# EasyPi_20210521.net
KiCad netlist of a schematic drawn in Altium Designer
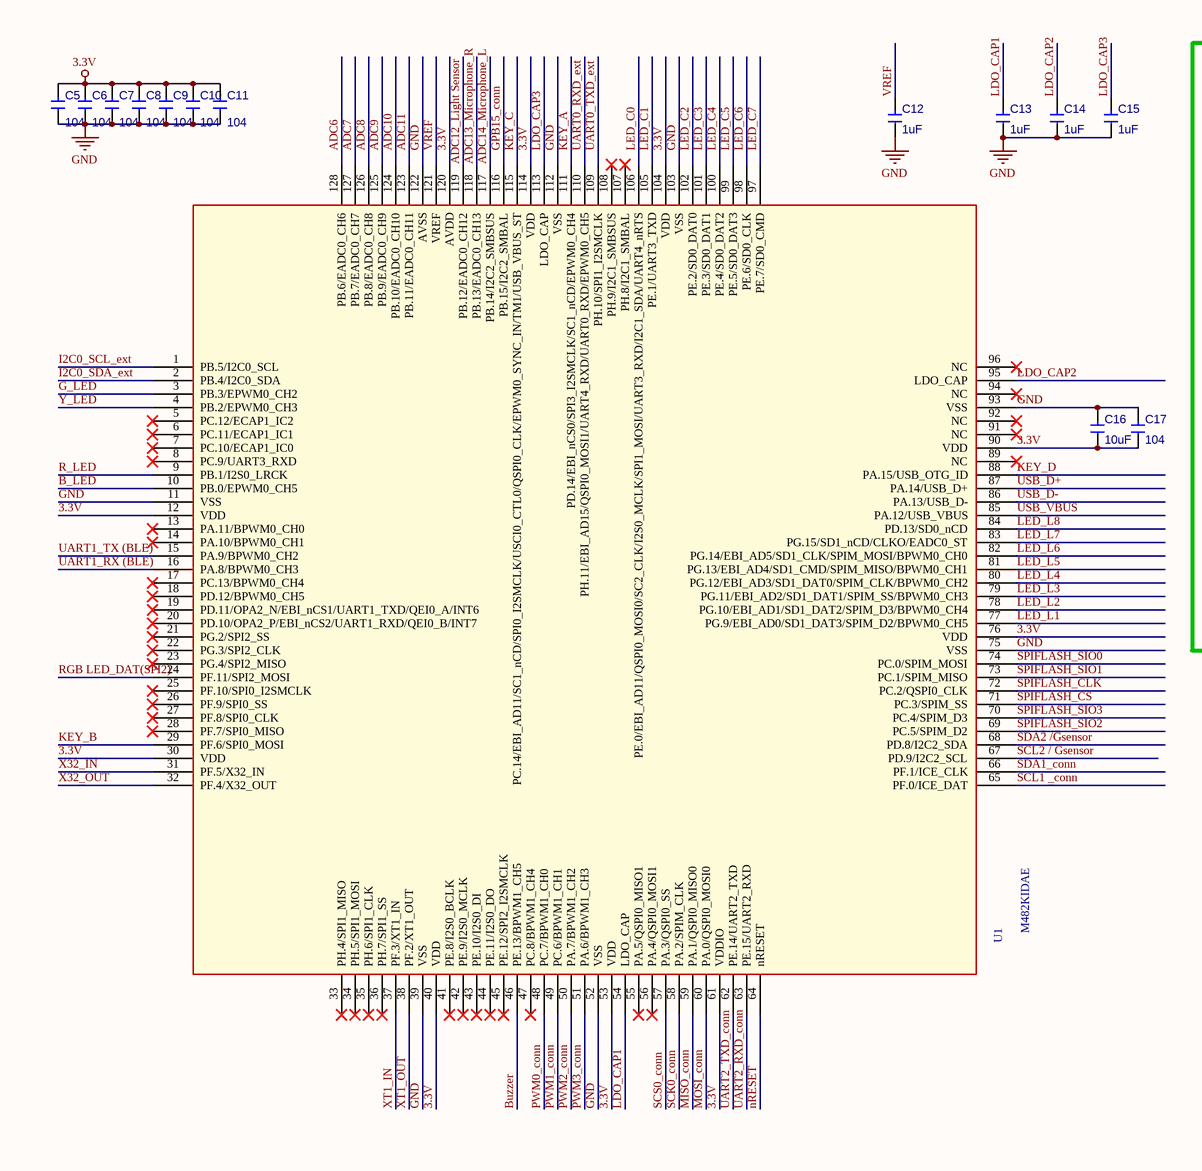
[diagram p0: EasyPi+ 20210521.SchDoc, top left]
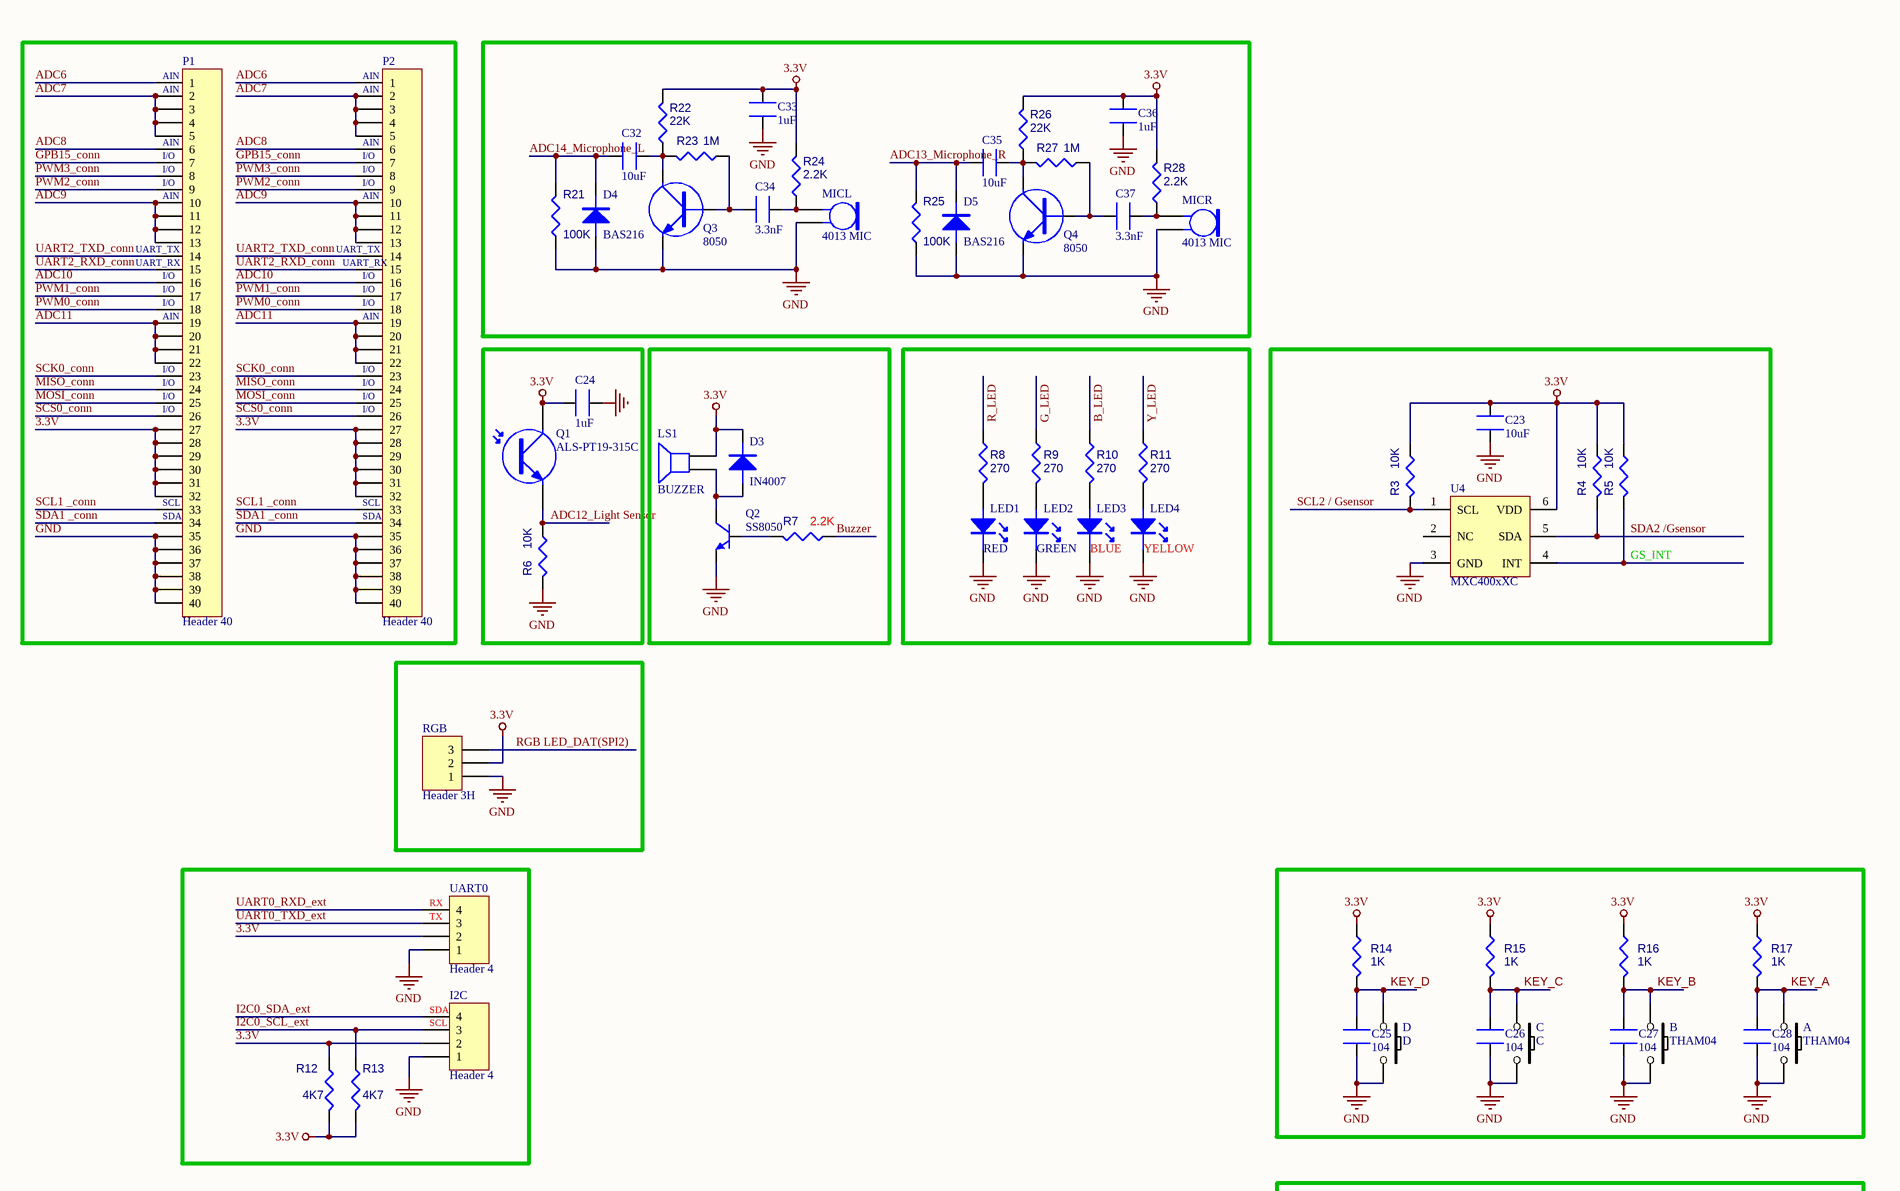
[diagram p1: EasyPi+ 20210521.SchDoc, top right]
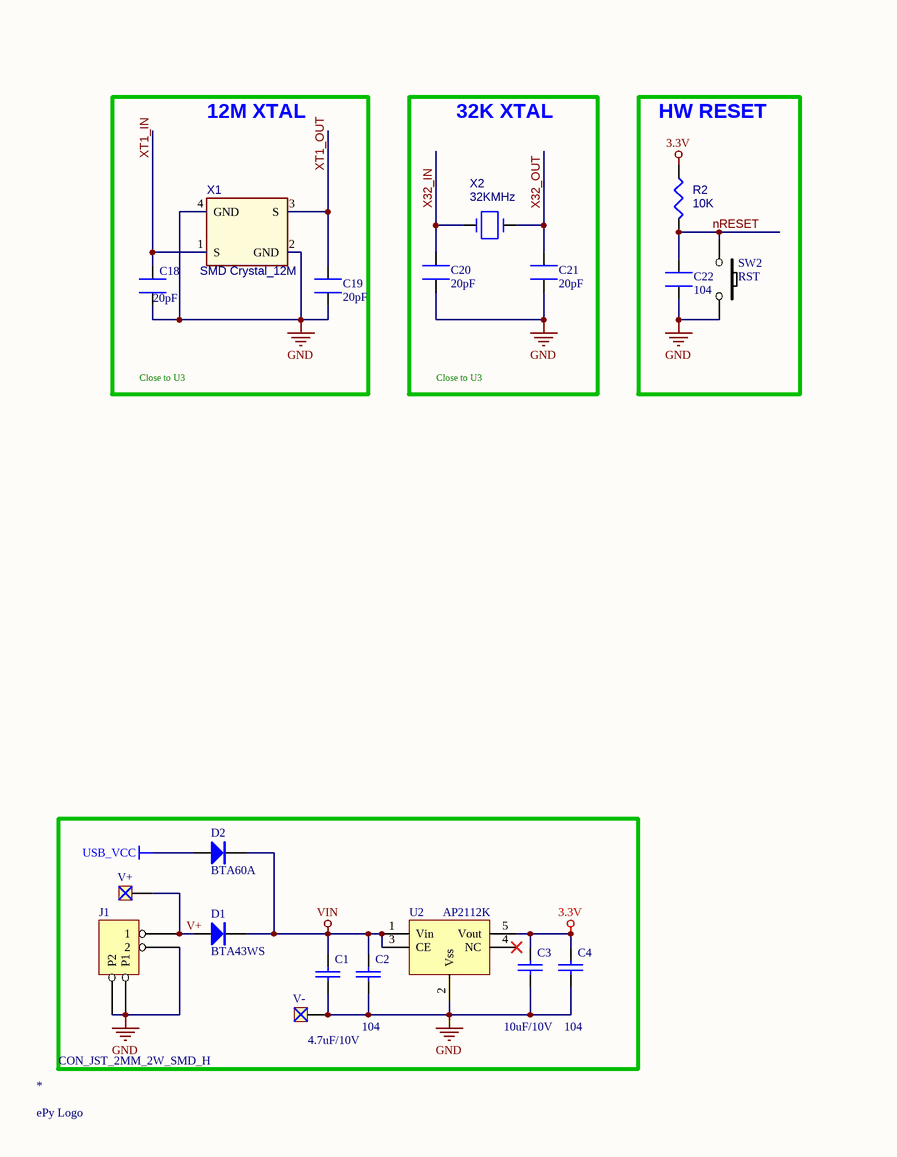
[diagram p2: EasyPi+ 20210521.SchDoc, bottom left]
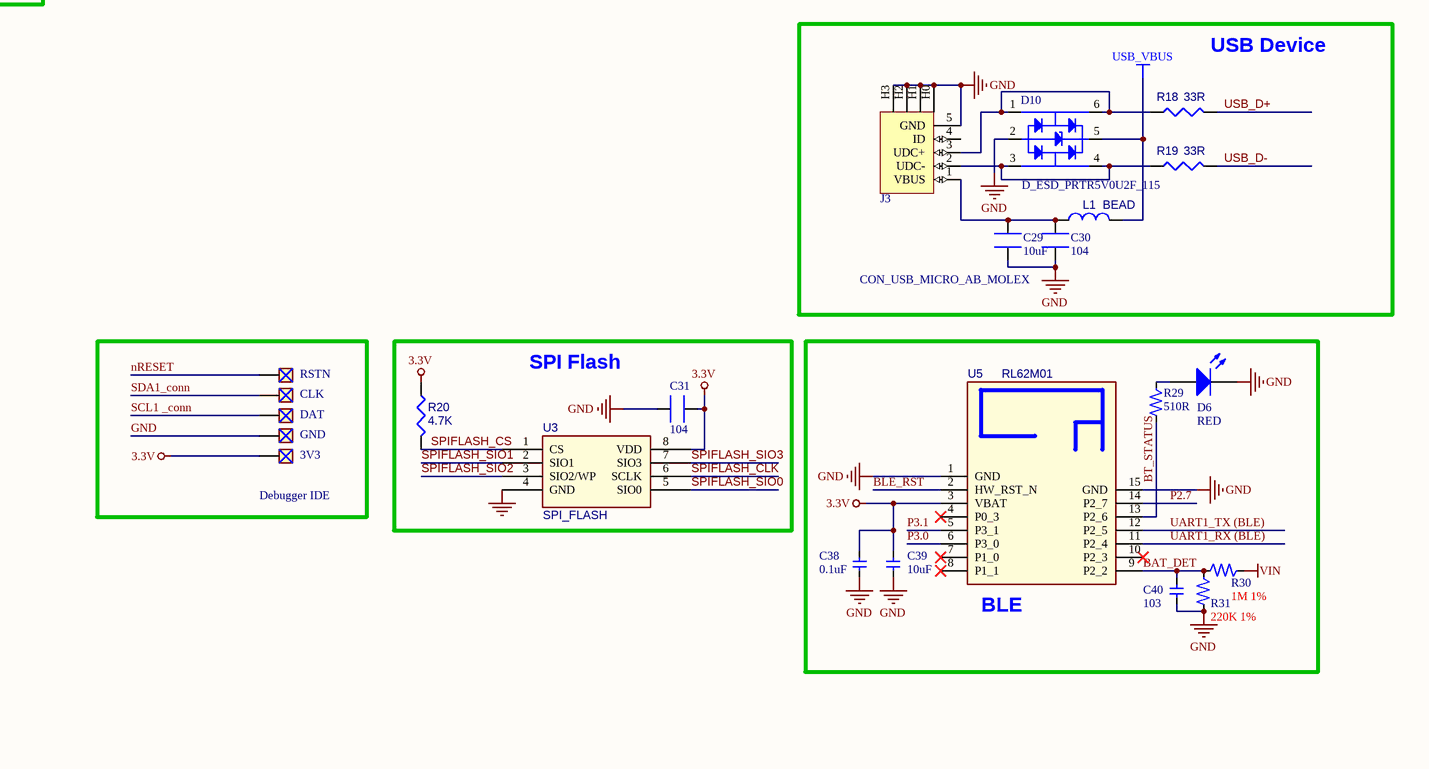
[diagram p3: EasyPi+ 20210521.SchDoc, bottom right]

(export (version "E")
  (design (tool "Eeschema 10.0.6"))
  (components
    (comp (ref "*") (value "ePy Logo") (footprint "ePi LOGO-M") (libsource (lib "Allen") (part "ePy Logo")))
    (comp (ref "3V3") (value "TERMINAL") (footprint "PAD-SMD") (libsource (lib "Allen") (part "TERMINAL")))
    (comp (ref "A") (value "THAM04") (footprint "TC-H-4415AA") (libsource (lib "Allen") (part "TC SWITCH")))
    (comp (ref "B") (value "THAM04") (footprint "TC-H-4415AA") (libsource (lib "Allen") (part "TC SWITCH")))
    (comp (ref "C") (value "C") (footprint "TC-H-4415AA") (libsource (lib "Allen") (part "TC SWITCH")))
    (comp (ref "C1")
      (value "4.7uF/10V")
      (footprint "C 0805")
      (description "CAP")
      (libsource (lib "") (part "CAP_1"))
    )
    (comp (ref "C2")
      (value "104")
      (footprint "C 0402")
      (description "CAP")
      (libsource (lib "") (part "CAP_1"))
    )
    (comp (ref "C3")
      (value "10uF/10V")
      (footprint "C 0402")
      (description "CAP")
      (libsource (lib "") (part "CAP_1"))
    )
    (comp (ref "C4")
      (value "104")
      (footprint "C 0402")
      (description "CAP")
      (libsource (lib "") (part "CAP_1"))
    )
    (comp (ref "C5")
      (value "104")
      (footprint "C 0402")
      (description "MC (R2HF) 1uF 10V 10%(K) X5R 0402 T=0.5mm CC0402KRX5R6BB105 YAGEO")
      (fields (field (name "PART_NUMBER") "150-226-0173R"))
      (libsource (lib "*") (part "CAP"))
    )
    (comp (ref "C6")
      (value "104")
      (footprint "C 0402")
      (description "MC (R2HF) 1uF 10V 10%(K) X5R 0402 T=0.5mm CC0402KRX5R6BB105 YAGEO")
      (fields (field (name "PART_NUMBER") "150-226-0173R"))
      (libsource (lib "*") (part "CAP"))
    )
    (comp (ref "C7")
      (value "104")
      (footprint "C 0402")
      (description "MC (R2HF) 1uF 10V 10%(K) X5R 0402 T=0.5mm CC0402KRX5R6BB105 YAGEO")
      (fields (field (name "PART_NUMBER") "150-226-0173R"))
      (libsource (lib "*") (part "CAP"))
    )
    (comp (ref "C8")
      (value "104")
      (footprint "C 0402")
      (description "MC (R2HF) 1uF 10V 10%(K) X5R 0402 T=0.5mm CC0402KRX5R6BB105 YAGEO")
      (fields (field (name "PART_NUMBER") "150-226-0173R"))
      (libsource (lib "*") (part "CAP"))
    )
    (comp (ref "C9")
      (value "104")
      (footprint "C 0402")
      (description "MC (R2HF) 1uF 10V 10%(K) X5R 0402 T=0.5mm CC0402KRX5R6BB105 YAGEO")
      (fields (field (name "PART_NUMBER") "150-226-0173R"))
      (libsource (lib "*") (part "CAP"))
    )
    (comp (ref "C10")
      (value "104")
      (footprint "C 0402")
      (description "MC (R2HF) 1uF 10V 10%(K) X5R 0402 T=0.5mm CC0402KRX5R6BB105 YAGEO")
      (fields (field (name "PART_NUMBER") "150-226-0173R"))
      (libsource (lib "*") (part "CAP"))
    )
    (comp (ref "C11")
      (value "104")
      (footprint "C 0402")
      (description "MC (R2HF) 1uF 10V 10%(K) X5R 0402 T=0.5mm CC0402KRX5R6BB105 YAGEO")
      (fields (field (name "PART_NUMBER") "150-226-0173R"))
      (libsource (lib "*") (part "CAP"))
    )
    (comp (ref "C12")
      (value "1uF")
      (footprint "C 0402")
      (description "MC (R2HF) 1uF 10V 10%(K) X5R 0402 T=0.5mm CC0402KRX5R6BB105 YAGEO")
      (fields (field (name "PART_NUMBER") "150-226-0173R"))
      (libsource (lib "*") (part "CAP"))
    )
    (comp (ref "C13")
      (value "1uF")
      (footprint "C 0402")
      (description "MC (R2HF) 1uF 10V 10%(K) X5R 0402 T=0.5mm CC0402KRX5R6BB105 YAGEO")
      (fields (field (name "PART_NUMBER") "150-226-0173R"))
      (libsource (lib "*") (part "CAP"))
    )
    (comp (ref "C14")
      (value "1uF")
      (footprint "C 0402")
      (description "MC (R2HF) 1uF 10V 10%(K) X5R 0402 T=0.5mm CC0402KRX5R6BB105 YAGEO")
      (fields (field (name "PART_NUMBER") "150-226-0173R"))
      (libsource (lib "*") (part "CAP"))
    )
    (comp (ref "C15")
      (value "1uF")
      (footprint "C 0402")
      (description "MC (R2HF) 1uF 10V 10%(K) X5R 0402 T=0.5mm CC0402KRX5R6BB105 YAGEO")
      (fields (field (name "PART_NUMBER") "150-226-0173R"))
      (libsource (lib "*") (part "CAP"))
    )
    (comp (ref "C16")
      (value "10uF")
      (footprint "C 0402")
      (description "MC (R2HF) 1uF 10V 10%(K) X5R 0402 T=0.5mm CC0402KRX5R6BB105 YAGEO")
      (fields (field (name "PART_NUMBER") "150-226-0173R"))
      (libsource (lib "*") (part "CAP"))
    )
    (comp (ref "C17")
      (value "104")
      (footprint "C 0402")
      (description "MC (R2HF) 1uF 10V 10%(K) X5R 0402 T=0.5mm CC0402KRX5R6BB105 YAGEO")
      (fields (field (name "PART_NUMBER") "150-226-0173R"))
      (libsource (lib "*") (part "CAP"))
    )
    (comp (ref "C18") (value "20pF") (footprint "C 0402") (libsource (lib "Allen") (part "CAP")))
    (comp (ref "C19") (value "20pF") (footprint "C 0402") (libsource (lib "Allen") (part "CAP")))
    (comp (ref "C20") (value "20pF") (footprint "C 0402") (libsource (lib "Allen") (part "CAP")))
    (comp (ref "C21") (value "20pF") (footprint "C 0402") (libsource (lib "Allen") (part "CAP")))
    (comp (ref "C22") (value "104") (footprint "C 0402") (libsource (lib "Allen") (part "CAP")))
    (comp (ref "C23") (value "10uF") (footprint "C 0402") (libsource (lib "Allen") (part "CAP")))
    (comp (ref "C24") (value "1uF") (footprint "C 0402") (libsource (lib "Allen") (part "CAP")))
    (comp (ref "C25") (value "104") (footprint "C 0402") (libsource (lib "Allen") (part "CAP")))
    (comp (ref "C26") (value "104") (footprint "C 0402") (libsource (lib "Allen") (part "CAP")))
    (comp (ref "C27") (value "104") (footprint "C 0402") (libsource (lib "Allen") (part "CAP")))
    (comp (ref "C28") (value "104") (footprint "C 0402") (libsource (lib "Allen") (part "CAP")))
    (comp (ref "C29") (value "10uF") (footprint "C 0402") (libsource (lib "Allen") (part "CAP")))
    (comp (ref "C30") (value "104") (footprint "C 0402") (libsource (lib "Allen") (part "CAP")))
    (comp (ref "C31") (value "104") (footprint "C 0603") (libsource (lib "Allen") (part "CAP")))
    (comp (ref "C32") (value "10uF") (footprint "C 0402") (libsource (lib "Allen") (part "CAP")))
    (comp (ref "C33") (value "1uF") (footprint "C 0402") (libsource (lib "Allen") (part "CAP")))
    (comp (ref "C34") (value "3.3nF") (footprint "C 0402") (libsource (lib "Allen") (part "CAP")))
    (comp (ref "C35") (value "10uF") (footprint "C 0402") (libsource (lib "Allen") (part "CAP")))
    (comp (ref "C36") (value "1uF") (footprint "C 0402") (libsource (lib "Allen") (part "CAP")))
    (comp (ref "C37") (value "3.3nF") (footprint "C 0402") (libsource (lib "Allen") (part "CAP")))
    (comp (ref "C38") (value "0.1uF") (footprint "C 0402") (libsource (lib "Allen") (part "CAP/S")))
    (comp (ref "C39") (value "10uF") (footprint "C 0402") (libsource (lib "Allen") (part "CAP/S")))
    (comp (ref "C40") (value "103") (footprint "C 0402") (libsource (lib "Allen") (part "CAP/S")))
    (comp (ref "CLK") (value "TERMINAL") (footprint "PAD-SMD") (libsource (lib "Allen") (part "TERMINAL")))
    (comp (ref "D") (value "D") (footprint "TC-H-4415AA") (libsource (lib "Allen") (part "TC SWITCH")))
    (comp (ref "D1")
      (value "BTA43WS")
      (footprint "SOD-323")
      (description "快恢复整流二极管")
      (fields (field (name "版权归属") "黎明电子style"))
      (libsource (lib "二极管-整流桥") (part "FFM107"))
    )
    (comp (ref "D2")
      (value "BTA60A")
      (footprint "SOD-323")
      (description "快恢复整流二极管")
      (fields (field (name "版权归属") "黎明电子style"))
      (libsource (lib "二极管-整流桥") (part "FFM107"))
    )
    (comp (ref "D3") (value "IN4007") (footprint "SOD-123F") (libsource (lib "Allen") (part "DIODE")))
    (comp (ref "D4") (value "BAS216") (footprint "SOD123") (libsource (lib "Allen") (part "DIODE")))
    (comp (ref "D5") (value "BAS216") (footprint "SOD123") (libsource (lib "Allen") (part "DIODE")))
    (comp (ref "D6")
      (value "RED")
      (footprint "LED 0603R")
      (description "Typical RED, GREEN, YELLOW, AMBER GaAs LED")
      (fields (field (name "PUBLISHER") "Altium Limited"))
      (libsource (lib "Miscellaneous Devices") (part "LED2"))
    )
    (comp (ref "D10")
      (value "D_ESD_PRTR5V0U2F_115")
      (footprint "SOT886")
      (description "Ultra low capacitance double rail-to-rail ESD protection")
      (fields (field (name "MANUFACTURER") "NXP") (field (name "PART") "PRTR5V0U2F_115"))
      (libsource (lib "Allen") (part "D_ESD_PRTR5V0U2F_115"))
    )
    (comp (ref "DAT") (value "TERMINAL") (footprint "PAD-SMD") (libsource (lib "Allen") (part "TERMINAL")))
    (comp (ref "GND") (value "TERMINAL") (footprint "PAD-SMD") (libsource (lib "Allen") (part "TERMINAL")))
    (comp (ref "I2C")
      (value "Header 4")
      (footprint "XH2.54-4P")
      (description "Header, 4-Pin")
      (fields (field (name "PUBLISHER") "Altium Limited"))
      (libsource (lib "Miscellaneous Connectors") (part "Header 4"))
    )
    (comp (ref "J1")
      (value "CON_JST_2MM_2W_SMD_H")
      (footprint "CON_JST_S2B-PH-SM4-TB")
      (description "2 PIN 2MM SMT JST  CONNECTOR")
      (fields (field (name "PART") "S2B-PH-SM4-TB(LF)(SN)") (field (name "MANUFACTURER") "JST"))
      (libsource (lib "Arbury_CON") (part "CON_JST_2MM_2W_SMD_H"))
    )
    (comp (ref "J3")
      (value "CON_USB_MICRO_AB_MOLEX")
      (footprint "CON_USB_MICRO_AB_MOLEX")
      (description "USB Micro-AB socket Molex 47589-0001")
      (fields (field (name "PART") "47589-0001") (field (name "MANUFACTURER") "Molex"))
      (libsource (lib "Allen") (part "CON_USB_MICRO_AB_MOLEX"))
    )
    (comp (ref "L1") (value "BEAD") (footprint "L 0603") (libsource (lib "*") (part "FB_0603")))
    (comp (ref "LED1") (value "RED") (footprint "LED-0603") (libsource (lib "Allen") (part "LED")))
    (comp (ref "LED2") (value "GREEN") (footprint "LED-0603") (libsource (lib "Allen") (part "LED")))
    (comp (ref "LED3") (value "BLUE") (footprint "LED-0603") (libsource (lib "Allen") (part "LED")))
    (comp (ref "LED4") (value "YELLOW") (footprint "LED-0603") (libsource (lib "Allen") (part "LED")))
    (comp (ref "LS1")
      (value "BUZZER")
      (footprint "BUZER 8530")
      (description "Loudspeaker")
      (fields (field (name "PUBLISHER") "Altium Limited"))
      (libsource (lib "Miscellaneous Devices") (part "Speaker"))
    )
    (comp (ref "MICL")
      (value "4013 MIC")
      (footprint "4013 MIC")
      (description "Microphone")
      (fields (field (name "PUBLISHER") "Altium Limited"))
      (libsource (lib "Miscellaneous Devices") (part "Mic2"))
    )
    (comp (ref "MICR")
      (value "4013 MIC")
      (footprint "4013 MIC")
      (description "Microphone")
      (fields (field (name "PUBLISHER") "Altium Limited"))
      (libsource (lib "Miscellaneous Devices") (part "Mic2"))
    )
    (comp (ref "P1")
      (value "Header 40")
      (footprint "HEADER40")
      (description "Header, 40-Pin")
      (fields (field (name "PUBLISHER") "Altium Limited"))
      (libsource (lib "Allen") (part "Header 40"))
    )
    (comp (ref "P2")
      (value "Header 40")
      (footprint "HEADER40")
      (description "Header, 40-Pin")
      (fields (field (name "PUBLISHER") "Altium Limited"))
      (libsource (lib "Allen") (part "Header 40"))
    )
    (comp (ref "Q1")
      (value "ALS-PT19-315C")
      (footprint "ALS-PT19-315C")
      (description "NPN Phototransistor")
      (fields (field (name "PUBLISHER") "Altium Limited"))
      (libsource (lib "Allen") (part "Photo NPN"))
    )
    (comp (ref "Q2")
      (value "SS8050")
      (footprint "SOT23-3N")
      (description "高频放大-NPN型")
      (fields (field (name "版权归属") "黎明电子style"))
      (libsource (lib "三极管") (part "8050-SMD"))
    )
    (comp (ref "Q3")
      (value "8050")
      (footprint "SOT23-3")
      (description "NPN")
      (libsource (lib "Allen") (part "NPN"))
    )
    (comp (ref "Q4")
      (value "8050")
      (footprint "SOT23-3")
      (description "NPN")
      (libsource (lib "Allen") (part "NPN"))
    )
    (comp (ref "R2") (value "10K") (footprint "R 0402") (libsource (lib "*") (part "R")))
    (comp (ref "R3") (value "10K") (footprint "R 0402") (libsource (lib "*") (part "R")))
    (comp (ref "R4") (value "10K") (footprint "R 0402") (libsource (lib "*") (part "R")))
    (comp (ref "R5") (value "10K") (footprint "R 0402") (libsource (lib "*") (part "R")))
    (comp (ref "R6") (value "10K") (footprint "R 0402") (libsource (lib "*") (part "R")))
    (comp (ref "R7") (value "2.2K") (footprint "R 0402") (libsource (lib "*") (part "R")))
    (comp (ref "R8") (value "270") (footprint "R 0402") (libsource (lib "*") (part "R")))
    (comp (ref "R9") (value "270") (footprint "R 0402") (libsource (lib "*") (part "R")))
    (comp (ref "R10") (value "270") (footprint "R 0402") (libsource (lib "*") (part "R")))
    (comp (ref "R11") (value "270") (footprint "R 0402") (libsource (lib "*") (part "R")))
    (comp (ref "R12") (value "4K7") (footprint "R 0402") (libsource (lib "*") (part "R")))
    (comp (ref "R13") (value "4K7") (footprint "R 0402") (libsource (lib "*") (part "R")))
    (comp (ref "R14") (value "1K") (footprint "R 0402") (libsource (lib "*") (part "R")))
    (comp (ref "R15") (value "1K") (footprint "R 0402") (libsource (lib "*") (part "R")))
    (comp (ref "R16") (value "1K") (footprint "R 0402") (libsource (lib "*") (part "R")))
    (comp (ref "R17") (value "1K") (footprint "R 0402") (libsource (lib "*") (part "R")))
    (comp (ref "R18") (value "33R") (footprint "R 0402") (libsource (lib "*") (part "R")))
    (comp (ref "R19") (value "33R") (footprint "R 0402") (libsource (lib "*") (part "R")))
    (comp (ref "R20") (value "4.7K") (footprint "R 0603") (libsource (lib "*") (part "R")))
    (comp (ref "R21") (value "100K") (footprint "R 0402") (libsource (lib "*") (part "R")))
    (comp (ref "R22") (value "22K") (footprint "R 0402") (libsource (lib "*") (part "R")))
    (comp (ref "R23") (value "1M") (footprint "R 0402") (libsource (lib "*") (part "R")))
    (comp (ref "R24") (value "2.2K") (footprint "R 0402") (libsource (lib "*") (part "R")))
    (comp (ref "R25") (value "100K") (footprint "R 0402") (libsource (lib "*") (part "R")))
    (comp (ref "R26") (value "22K") (footprint "R 0402") (libsource (lib "*") (part "R")))
    (comp (ref "R27") (value "1M") (footprint "R 0402") (libsource (lib "*") (part "R")))
    (comp (ref "R28") (value "2.2K") (footprint "R 0402") (libsource (lib "*") (part "R")))
    (comp (ref "R29") (value "510R") (footprint "R 0402") (libsource (lib "Allen") (part "RES1_30")))
    (comp (ref "R30") (value "1M 1%") (footprint "R 0603") (libsource (lib "Allen") (part "RES1_30")))
    (comp (ref "R31") (value "220K 1%") (footprint "R 0603") (libsource (lib "Allen") (part "RES1_30")))
    (comp (ref "RGB")
      (value "Header 3H")
      (footprint "A1254WR-S-03P")
      (description "Header, 3-Pin, Right Angle")
      (fields (field (name "PUBLISHER") "Altium Limited"))
      (libsource (lib "Miscellaneous Connectors") (part "Header 3H"))
    )
    (comp (ref "RSTN") (value "TERMINAL") (footprint "PAD-SMD") (libsource (lib "Allen") (part "TERMINAL")))
    (comp (ref "SW2")
      (value "RST")
      (footprint "T.SW/SMD/3x4 - NP")
      (libsource (lib "Allen") (part "TC SWITCH"))
    )
    (comp (ref "U1")
      (value "M482KIDAE")
      (footprint "LQFP128 14x14_N")
      (libsource (lib "M482KIDAE") (part "M482KIDAE"))
    )
    (comp (ref "U2") (value "AP2112K") (footprint "SOT23-5L") (libsource (lib "Allen") (part "XC6204")))
    (comp (ref "U3")
      (value "SPI_FLASH")
      (footprint "VSOP8 - 208mil")
      (description "IC FLASH (R) GD25Q128CSIG SOP-8 128MX1/64MX2/32MX4 2.7~3.6V SPI INDUSTRIAL GIGADEVICE")
      (libsource (lib "*") (part "FLASH-Serial 8pin-91_0"))
    )
    (comp (ref "U4") (value "MXC400xXC") (footprint "MXC400xXC") (libsource (lib "Allen") (part "MXC400xXC")))
    (comp (ref "U5") (value "RL62M01") (footprint "RL62M01A") (libsource (lib "Allen") (part "RL62M01")))
    (comp (ref "UART0")
      (value "Header 4")
      (footprint "XH2.54-4P")
      (description "Header, 4-Pin")
      (fields (field (name "PUBLISHER") "Altium Limited"))
      (libsource (lib "Miscellaneous Connectors") (part "Header 4"))
    )
    (comp (ref "V+") (value "PIN") (footprint "PAD-SMD") (libsource (lib "Allen") (part "PIN")))
    (comp (ref "V-") (value "PIN1") (footprint "PAD-SMD") (libsource (lib "Allen") (part "PIN")))
    (comp (ref "X1")
      (value "SMD Crystal_12M")
      (footprint "XTAL-3225")
      (libsource (lib "*") (part "XTAL_SMD"))
    )
    (comp (ref "X2") (value "32KMHz") (footprint "XTAL-3215") (libsource (lib "*") (part "CRYSTAL/SM")))
  )
  (nets
    (net (code "1") (name "/ADC6") (class "Default")
      (node (ref "P1") (pin "1") (pinfunction "1_1") (pintype "passive"))
      (node (ref "P2") (pin "1") (pinfunction "1_1") (pintype "passive"))
      (node (ref "U1") (pin "128") (pinfunction "PB.6/EADC0_CH6_128") (pintype "passive"))
    )
    (net (code "2") (name "/ADC7") (class "Default")
      (node (ref "P1") (pin "2") (pinfunction "2_2") (pintype "passive"))
      (node (ref "P1") (pin "3") (pinfunction "3_3") (pintype "passive"))
      (node (ref "P1") (pin "4") (pinfunction "4_4") (pintype "passive"))
      (node (ref "P1") (pin "5") (pinfunction "5_5") (pintype "passive"))
      (node (ref "P2") (pin "2") (pinfunction "2_2") (pintype "passive"))
      (node (ref "P2") (pin "3") (pinfunction "3_3") (pintype "passive"))
      (node (ref "P2") (pin "4") (pinfunction "4_4") (pintype "passive"))
      (node (ref "P2") (pin "5") (pinfunction "5_5") (pintype "passive"))
      (node (ref "U1") (pin "127") (pinfunction "PB.7/EADC0_CH7_127") (pintype "passive"))
    )
    (net (code "3") (name "/ADC8") (class "Default")
      (node (ref "P1") (pin "6") (pinfunction "6_6") (pintype "passive"))
      (node (ref "P2") (pin "6") (pinfunction "6_6") (pintype "passive"))
      (node (ref "U1") (pin "126") (pinfunction "PB.8/EADC0_CH8_126") (pintype "passive"))
    )
    (net (code "4") (name "/ADC9") (class "Default")
      (node (ref "P1") (pin "10") (pinfunction "10_10") (pintype "passive"))
      (node (ref "P1") (pin "11") (pinfunction "11_11") (pintype "passive"))
      (node (ref "P1") (pin "12") (pinfunction "12_12") (pintype "passive"))
      (node (ref "P1") (pin "13") (pinfunction "13_13") (pintype "passive"))
      (node (ref "P2") (pin "10") (pinfunction "10_10") (pintype "passive"))
      (node (ref "P2") (pin "11") (pinfunction "11_11") (pintype "passive"))
      (node (ref "P2") (pin "12") (pinfunction "12_12") (pintype "passive"))
      (node (ref "P2") (pin "13") (pinfunction "13_13") (pintype "passive"))
      (node (ref "U1") (pin "125") (pinfunction "PB.9/EADC0_CH9_125") (pintype "passive"))
    )
    (net (code "5") (name "/ADC10") (class "Default")
      (node (ref "P1") (pin "16") (pinfunction "16_16") (pintype "passive"))
      (node (ref "P2") (pin "16") (pinfunction "16_16") (pintype "passive"))
      (node (ref "U1") (pin "124") (pinfunction "PB.10/EADC0_CH10_124") (pintype "passive"))
    )
    (net (code "6") (name "/ADC11") (class "Default")
      (node (ref "P1") (pin "19") (pinfunction "19_19") (pintype "passive"))
      (node (ref "P1") (pin "20") (pinfunction "20_20") (pintype "passive"))
      (node (ref "P1") (pin "21") (pinfunction "21_21") (pintype "passive"))
      (node (ref "P1") (pin "22") (pinfunction "22_22") (pintype "passive"))
      (node (ref "P2") (pin "19") (pinfunction "19_19") (pintype "passive"))
      (node (ref "P2") (pin "20") (pinfunction "20_20") (pintype "passive"))
      (node (ref "P2") (pin "21") (pinfunction "21_21") (pintype "passive"))
      (node (ref "P2") (pin "22") (pinfunction "22_22") (pintype "passive"))
      (node (ref "U1") (pin "123") (pinfunction "PB.11/EADC0_CH11_123") (pintype "passive"))
    )
    (net (code "7") (name "/ADC12_Light Sensor") (class "Default")
      (node (ref "Q1") (pin "2") (pinfunction "2_2") (pintype "passive"))
      (node (ref "R6") (pin "1") (pinfunction "1_1") (pintype "passive"))
      (node (ref "U1") (pin "119") (pinfunction "PB.12/EADC0_CH12_119") (pintype "passive"))
    )
    (net (code "8") (name "/ADC13_Microphone_R") (class "Default")
      (node (ref "C35") (pin "1") (pinfunction "1_1") (pintype "passive"))
      (node (ref "D5") (pin "2") (pinfunction "K_2") (pintype "passive"))
      (node (ref "R25") (pin "2") (pinfunction "2_2") (pintype "passive"))
      (node (ref "U1") (pin "118") (pinfunction "PB.13/EADC0_CH13_118") (pintype "passive"))
    )
    (net (code "9") (name "/ADC14_Microphone_L") (class "Default")
      (node (ref "C32") (pin "1") (pinfunction "1_1") (pintype "passive"))
      (node (ref "D4") (pin "2") (pinfunction "K_2") (pintype "passive"))
      (node (ref "R21") (pin "2") (pinfunction "2_2") (pintype "passive"))
      (node (ref "U1") (pin "117") (pinfunction "PB.14/I2C2_SMBSUS_117") (pintype "passive"))
    )
    (net (code "10") (name "/BAT_DET") (class "Default")
      (node (ref "C40") (pin "1") (pinfunction "1_1") (pintype "passive"))
      (node (ref "R30") (pin "1") (pintype "passive"))
      (node (ref "R31") (pin "2") (pintype "passive"))
      (node (ref "U5") (pin "9") (pinfunction "P2_2_9") (pintype "passive"))
    )
    (net (code "11") (name "/BLE_RST") (class "Default")
      (node (ref "U5") (pin "2") (pinfunction "HW_RST_N_2") (pintype "passive"))
    )
    (net (code "12") (name "/BT_STATUS") (class "Default")
      (node (ref "R29") (pin "1") (pintype "passive"))
      (node (ref "U5") (pin "13") (pinfunction "P2_6_13") (pintype "passive"))
    )
    (net (code "13") (name "/B_LED") (class "Default")
      (node (ref "R10") (pin "1") (pinfunction "1_1") (pintype "passive"))
      (node (ref "U1") (pin "10") (pinfunction "PB.0/EPWM0_CH5_10") (pintype "passive"))
    )
    (net (code "14") (name "/Buzzer") (class "Default")
      (node (ref "R7") (pin "1") (pinfunction "1_1") (pintype "passive"))
      (node (ref "U1") (pin "46") (pinfunction "PE.13/BPWM1_CH5_46") (pintype "passive"))
    )
    (net (code "15") (name "/GPB15_conn") (class "Default")
      (node (ref "P1") (pin "7") (pinfunction "7_7") (pintype "passive"))
      (node (ref "P2") (pin "7") (pinfunction "7_7") (pintype "passive"))
      (node (ref "U1") (pin "116") (pinfunction "PB.15/I2C2_SMBAL_116") (pintype "passive"))
    )
    (net (code "16") (name "/GS_INT") (class "Default")
      (node (ref "R5") (pin "2") (pinfunction "2_2") (pintype "passive"))
      (node (ref "U4") (pin "4") (pinfunction "INT_4") (pintype "passive"))
    )
    (net (code "17") (name "/G_LED") (class "Default")
      (node (ref "R9") (pin "1") (pinfunction "1_1") (pintype "passive"))
      (node (ref "U1") (pin "3") (pinfunction "PB.3/EPWM0_CH2_3") (pintype "passive"))
    )
    (net (code "18") (name "/I2C0_SCL_ext") (class "Default")
      (node (ref "I2C") (pin "3") (pinfunction "3_3") (pintype "passive"))
      (node (ref "R13") (pin "1") (pinfunction "1_1") (pintype "passive"))
      (node (ref "U1") (pin "1") (pinfunction "PB.5/I2C0_SCL_1") (pintype "passive"))
    )
    (net (code "19") (name "/I2C0_SDA_ext") (class "Default")
      (node (ref "I2C") (pin "4") (pinfunction "4_4") (pintype "passive"))
      (node (ref "U1") (pin "2") (pinfunction "PB.4/I2C0_SDA_2") (pintype "passive"))
    )
    (net (code "20") (name "/KEY_A") (class "Default")
      (node (ref "A") (pin "1") (pinfunction "1_1") (pintype "passive"))
      (node (ref "C28") (pin "1") (pinfunction "1_1") (pintype "passive"))
      (node (ref "R17") (pin "2") (pinfunction "2_2") (pintype "passive"))
      (node (ref "U1") (pin "111") (pinfunction "PD.14/EBI_nCS0/SPI3_I2SMCLK/SC1_nCD/EPWM0_CH4_111") (pintype "passive"))
    )
    (net (code "21") (name "/KEY_B") (class "Default")
      (node (ref "B") (pin "1") (pinfunction "1_1") (pintype "passive"))
      (node (ref "C27") (pin "1") (pinfunction "1_1") (pintype "passive"))
      (node (ref "R16") (pin "2") (pinfunction "2_2") (pintype "passive"))
      (node (ref "U1") (pin "29") (pinfunction "PF.6/SPI0_MOSI_29") (pintype "passive"))
    )
    (net (code "22") (name "/KEY_C") (class "Default")
      (node (ref "C") (pin "1") (pinfunction "1_1") (pintype "passive"))
      (node (ref "C26") (pin "1") (pinfunction "1_1") (pintype "passive"))
      (node (ref "R15") (pin "2") (pinfunction "2_2") (pintype "passive"))
      (node (ref "U1") (pin "115") (pinfunction "PC.14/EBI_AD11/SC1_nCD/SPI0_I2SMCLK/USCI0_CTL0/QSPI0_CLK/EPWM0_SYNC_IN/TM1/USB_VBUS_ST_115") (pintype "passive"))
    )
    (net (code "23") (name "/KEY_D") (class "Default")
      (node (ref "C25") (pin "1") (pinfunction "1_1") (pintype "passive"))
      (node (ref "D") (pin "1") (pinfunction "1_1") (pintype "passive"))
      (node (ref "R14") (pin "2") (pinfunction "2_2") (pintype "passive"))
      (node (ref "U1") (pin "88") (pinfunction "PA.15/USB_OTG_ID_88") (pintype "passive"))
    )
    (net (code "24") (name "/LDO_CAP1") (class "Default")
      (node (ref "C13") (pin "2") (pinfunction "2_2") (pintype "passive"))
      (node (ref "U1") (pin "54") (pinfunction "LDO_CAP_54") (pintype "passive"))
    )
    (net (code "25") (name "/LDO_CAP2") (class "Default")
      (node (ref "C14") (pin "2") (pinfunction "2_2") (pintype "passive"))
      (node (ref "U1") (pin "95") (pinfunction "LDO_CAP_95") (pintype "passive"))
    )
    (net (code "26") (name "/LDO_CAP3") (class "Default")
      (node (ref "C15") (pin "2") (pinfunction "2_2") (pintype "passive"))
      (node (ref "U1") (pin "113") (pinfunction "LDO_CAP_113") (pintype "passive"))
    )
    (net (code "27") (name "/LED_C0") (class "Default")
      (node (ref "U1") (pin "106") (pinfunction "PE.0/EBI_AD11/QSPI0_MOSI0/SC2_CLK/I2S0_MCLK/SPI1_MOSI/UART3_RXD/I2C1_SDA/UART4_nRTS_106") (pintype "passive"))
    )
    (net (code "28") (name "/LED_C1") (class "Default")
      (node (ref "U1") (pin "105") (pinfunction "PE.1/UART3_TXD_105") (pintype "passive"))
    )
    (net (code "29") (name "/LED_C2") (class "Default")
      (node (ref "U1") (pin "102") (pinfunction "PE.2/SD0_DAT0_102") (pintype "passive"))
    )
    (net (code "30") (name "/LED_C3") (class "Default")
      (node (ref "U1") (pin "101") (pinfunction "PE.3/SD0_DAT1_101") (pintype "passive"))
    )
    (net (code "31") (name "/LED_C4") (class "Default")
      (node (ref "U1") (pin "100") (pinfunction "PE.4/SD0_DAT2_100") (pintype "passive"))
    )
    (net (code "32") (name "/LED_C5") (class "Default")
      (node (ref "U1") (pin "99") (pinfunction "PE.5/SD0_DAT3_99") (pintype "passive"))
    )
    (net (code "33") (name "/LED_C6") (class "Default")
      (node (ref "U1") (pin "98") (pinfunction "PE.6/SD0_CLK_98") (pintype "passive"))
    )
    (net (code "34") (name "/LED_C7") (class "Default")
      (node (ref "U1") (pin "97") (pinfunction "PE.7/SD0_CMD_97") (pintype "passive"))
    )
    (net (code "35") (name "/LED_L1") (class "Default")
      (node (ref "U1") (pin "77") (pinfunction "PG.9/EBI_AD0/SD1_DAT3/SPIM_D2/BPWM0_CH5_77") (pintype "passive"))
    )
    (net (code "36") (name "/LED_L2") (class "Default")
      (node (ref "U1") (pin "78") (pinfunction "PG.10/EBI_AD1/SD1_DAT2/SPIM_D3/BPWM0_CH4_78") (pintype "passive"))
    )
    (net (code "37") (name "/LED_L3") (class "Default")
      (node (ref "U1") (pin "79") (pinfunction "PG.11/EBI_AD2/SD1_DAT1/SPIM_SS/BPWM0_CH3_79") (pintype "passive"))
    )
    (net (code "38") (name "/LED_L4") (class "Default")
      (node (ref "U1") (pin "80") (pinfunction "PG.12/EBI_AD3/SD1_DAT0/SPIM_CLK/BPWM0_CH2_80") (pintype "passive"))
    )
    (net (code "39") (name "/LED_L5") (class "Default")
      (node (ref "U1") (pin "81") (pinfunction "PG.13/EBI_AD4/SD1_CMD/SPIM_MISO/BPWM0_CH1_81") (pintype "passive"))
    )
    (net (code "40") (name "/LED_L6") (class "Default")
      (node (ref "U1") (pin "82") (pinfunction "PG.14/EBI_AD5/SD1_CLK/SPIM_MOSI/BPWM0_CH0_82") (pintype "passive"))
    )
    (net (code "41") (name "/LED_L7") (class "Default")
      (node (ref "U1") (pin "83") (pinfunction "PG.15/SD1_nCD/CLKO/EADC0_ST_83") (pintype "passive"))
    )
    (net (code "42") (name "/LED_L8") (class "Default")
      (node (ref "U1") (pin "84") (pinfunction "PD.13/SD0_nCD_84") (pintype "passive"))
    )
    (net (code "43") (name "/MISO_conn") (class "Default")
      (node (ref "P1") (pin "24") (pinfunction "24_24") (pintype "passive"))
      (node (ref "P2") (pin "24") (pinfunction "24_24") (pintype "passive"))
      (node (ref "U1") (pin "59") (pinfunction "PA.1/QSPI0_MISO0_59") (pintype "passive"))
    )
    (net (code "44") (name "/MOSI_conn") (class "Default")
      (node (ref "P1") (pin "25") (pinfunction "25_25") (pintype "passive"))
      (node (ref "P2") (pin "25") (pinfunction "25_25") (pintype "passive"))
      (node (ref "U1") (pin "60") (pinfunction "PA.0/QSPI0_MOSI0_60") (pintype "passive"))
    )
    (net (code "45") (name "/P2.7") (class "Default")
      (node (ref "U5") (pin "14") (pinfunction "P2_7_14") (pintype "passive"))
    )
    (net (code "46") (name "/P3.0") (class "Default")
      (node (ref "U5") (pin "6") (pinfunction "P3_0_6") (pintype "passive"))
    )
    (net (code "47") (name "/P3.1") (class "Default")
      (node (ref "U5") (pin "5") (pinfunction "P3_1_5") (pintype "passive"))
    )
    (net (code "48") (name "/PWM0_conn") (class "Default")
      (node (ref "P1") (pin "18") (pinfunction "18_18") (pintype "passive"))
      (node (ref "P2") (pin "18") (pinfunction "18_18") (pintype "passive"))
      (node (ref "U1") (pin "48") (pinfunction "PC.7/BPWM1_CH0_48") (pintype "passive"))
    )
    (net (code "49") (name "/PWM1_conn") (class "Default")
      (node (ref "P1") (pin "17") (pinfunction "17_17") (pintype "passive"))
      (node (ref "P2") (pin "17") (pinfunction "17_17") (pintype "passive"))
      (node (ref "U1") (pin "49") (pinfunction "PC.6/BPWM1_CH1_49") (pintype "passive"))
    )
    (net (code "50") (name "/PWM2_conn") (class "Default")
      (node (ref "P1") (pin "9") (pinfunction "9_9") (pintype "passive"))
      (node (ref "P2") (pin "9") (pinfunction "9_9") (pintype "passive"))
      (node (ref "U1") (pin "50") (pinfunction "PA.7/BPWM1_CH2_50") (pintype "passive"))
    )
    (net (code "51") (name "/PWM3_conn") (class "Default")
      (node (ref "P1") (pin "8") (pinfunction "8_8") (pintype "passive"))
      (node (ref "P2") (pin "8") (pinfunction "8_8") (pintype "passive"))
      (node (ref "U1") (pin "51") (pinfunction "PA.6/BPWM1_CH3_51") (pintype "passive"))
    )
    (net (code "52") (name "/RGB LED_DAT(SPI2)") (class "Default")
      (node (ref "RGB") (pin "3") (pinfunction "3_3") (pintype "passive"))
      (node (ref "U1") (pin "24") (pinfunction "PF.11/SPI2_MOSI_24") (pintype "passive"))
    )
    (net (code "53") (name "/R_LED") (class "Default")
      (node (ref "R8") (pin "1") (pinfunction "1_1") (pintype "passive"))
      (node (ref "U1") (pin "9") (pinfunction "PB.1/I2S0_LRCK_9") (pintype "passive"))
    )
    (net (code "54") (name "/SCK0_conn") (class "Default")
      (node (ref "P1") (pin "23") (pinfunction "23_23") (pintype "passive"))
      (node (ref "P2") (pin "23") (pinfunction "23_23") (pintype "passive"))
      (node (ref "U1") (pin "58") (pinfunction "PA.2/SPIM_CLK_58") (pintype "passive"))
    )
    (net (code "55") (name "/SCL1 _conn") (class "Default")
      (node (ref "DAT") (pin "1") (pinfunction "1_1") (pintype "passive"))
      (node (ref "P1") (pin "33") (pinfunction "33_33") (pintype "passive"))
      (node (ref "P2") (pin "33") (pinfunction "33_33") (pintype "passive"))
      (node (ref "U1") (pin "65") (pinfunction "PF.0/ICE_DAT_65") (pintype "passive"))
    )
    (net (code "56") (name "/SCL2 {slash} Gsensor") (class "Default")
      (node (ref "R3") (pin "2") (pinfunction "2_2") (pintype "passive"))
      (node (ref "U1") (pin "67") (pinfunction "PD.9/I2C2_SCL_67") (pintype "passive"))
      (node (ref "U4") (pin "1") (pinfunction "SCL_1") (pintype "passive"))
    )
    (net (code "57") (name "/SCS0_conn") (class "Default")
      (node (ref "P1") (pin "26") (pinfunction "26_26") (pintype "passive"))
      (node (ref "P2") (pin "26") (pinfunction "26_26") (pintype "passive"))
      (node (ref "U1") (pin "57") (pinfunction "PA.3/QSPI0_SS_57") (pintype "passive"))
    )
    (net (code "58") (name "/SDA1 _conn") (class "Default")
      (node (ref "P1") (pin "34") (pinfunction "34_34") (pintype "passive"))
      (node (ref "P2") (pin "34") (pinfunction "34_34") (pintype "passive"))
    )
    (net (code "59") (name "/SDA1_conn") (class "Default")
      (node (ref "CLK") (pin "1") (pinfunction "1_1") (pintype "passive"))
      (node (ref "U1") (pin "66") (pinfunction "PF.1/ICE_CLK_66") (pintype "passive"))
    )
    (net (code "60") (name "/SDA2 {slash}Gsensor") (class "Default")
      (node (ref "R4") (pin "2") (pinfunction "2_2") (pintype "passive"))
      (node (ref "U1") (pin "68") (pinfunction "PD.8/I2C2_SDA_68") (pintype "passive"))
      (node (ref "U4") (pin "5") (pinfunction "SDA_5") (pintype "passive"))
    )
    (net (code "61") (name "/SPIFLASH_CLK") (class "Default")
      (node (ref "U1") (pin "72") (pinfunction "PC.2/QSPI0_CLK_72") (pintype "passive"))
      (node (ref "U3") (pin "6") (pinfunction "SCLK_6") (pintype "passive"))
    )
    (net (code "62") (name "/SPIFLASH_CS") (class "Default")
      (node (ref "R20") (pin "2") (pinfunction "2_2") (pintype "passive"))
      (node (ref "U1") (pin "71") (pinfunction "PC.3/SPIM_SS_71") (pintype "passive"))
      (node (ref "U3") (pin "1") (pinfunction "CS_1") (pintype "passive"))
    )
    (net (code "63") (name "/SPIFLASH_SIO0") (class "Default")
      (node (ref "U1") (pin "74") (pinfunction "PC.0/SPIM_MOSI_74") (pintype "passive"))
      (node (ref "U3") (pin "5") (pinfunction "SIO0_5") (pintype "passive"))
    )
    (net (code "64") (name "/SPIFLASH_SIO1") (class "Default")
      (node (ref "U1") (pin "73") (pinfunction "PC.1/SPIM_MISO_73") (pintype "passive"))
      (node (ref "U3") (pin "2") (pinfunction "SIO1_2") (pintype "passive"))
    )
    (net (code "65") (name "/SPIFLASH_SIO2") (class "Default")
      (node (ref "U1") (pin "69") (pinfunction "PC.5/SPIM_D2_69") (pintype "passive"))
      (node (ref "U3") (pin "3") (pinfunction "SIO2/WP_3") (pintype "passive"))
    )
    (net (code "66") (name "/SPIFLASH_SIO3") (class "Default")
      (node (ref "U1") (pin "70") (pinfunction "PC.4/SPIM_D3_70") (pintype "passive"))
      (node (ref "U3") (pin "7") (pinfunction "SIO3_7") (pintype "passive"))
    )
    (net (code "67") (name "/UART0_RXD_ext") (class "Default")
      (node (ref "U1") (pin "110") (pinfunction "PH.11/EBI_AD15/QSPI0_MOSI1/UART4_RXD/UART0_RXD/EPWM0_CH5_110") (pintype "passive"))
      (node (ref "UART0") (pin "4") (pinfunction "4_4") (pintype "passive"))
    )
    (net (code "68") (name "/UART0_TXD_ext") (class "Default")
      (node (ref "U1") (pin "109") (pinfunction "PH.10/SPI1_I2SMCLK_109") (pintype "passive"))
      (node (ref "UART0") (pin "3") (pinfunction "3_3") (pintype "passive"))
    )
    (net (code "69") (name "/UART1_RX (BLE)") (class "Default")
      (node (ref "U1") (pin "16") (pinfunction "PA.8/BPWM0_CH3_16") (pintype "passive"))
      (node (ref "U5") (pin "11") (pinfunction "P2_4_11") (pintype "passive"))
    )
    (net (code "70") (name "/UART1_TX (BLE)") (class "Default")
      (node (ref "U1") (pin "15") (pinfunction "PA.9/BPWM0_CH2_15") (pintype "passive"))
      (node (ref "U5") (pin "12") (pinfunction "P2_5_12") (pintype "passive"))
    )
    (net (code "71") (name "/UART2_RXD_conn") (class "Default")
      (node (ref "P1") (pin "15") (pinfunction "15_15") (pintype "passive"))
      (node (ref "P2") (pin "15") (pinfunction "15_15") (pintype "passive"))
      (node (ref "U1") (pin "63") (pinfunction "PE.15/UART2_RXD_63") (pintype "passive"))
    )
    (net (code "72") (name "/UART2_TXD_conn") (class "Default")
      (node (ref "P1") (pin "14") (pinfunction "14_14") (pintype "passive"))
      (node (ref "P2") (pin "14") (pinfunction "14_14") (pintype "passive"))
      (node (ref "U1") (pin "62") (pinfunction "PE.14/UART2_TXD_62") (pintype "passive"))
    )
    (net (code "73") (name "/USB_D+") (class "Default")
      (node (ref "R18") (pin "2") (pinfunction "2_2") (pintype "passive"))
      (node (ref "U1") (pin "87") (pinfunction "PA.14/USB_D+_87") (pintype "passive"))
    )
    (net (code "74") (name "/USB_D-") (class "Default")
      (node (ref "R19") (pin "2") (pinfunction "2_2") (pintype "passive"))
      (node (ref "U1") (pin "86") (pinfunction "PA.13/USB_D-_86") (pintype "passive"))
    )
    (net (code "75") (name "/V+") (class "Default")
      (node (ref "D1") (pin "1") (pinfunction "A_1") (pintype "passive"))
      (node (ref "J1") (pin "1") (pinfunction "1_1") (pintype "passive"))
      (node (ref "V+") (pin "1") (pinfunction "1_1") (pintype "passive"))
    )
    (net (code "76") (name "/VREF") (class "Default")
      (node (ref "C12") (pin "2") (pinfunction "2_2") (pintype "passive"))
      (node (ref "U1") (pin "121") (pinfunction "VREF_121") (pintype "passive"))
    )
    (net (code "77") (name "/X32_IN") (class "Default")
      (node (ref "C20") (pin "1") (pinfunction "1_1") (pintype "passive"))
      (node (ref "U1") (pin "31") (pinfunction "PF.5/X32_IN_31") (pintype "passive"))
      (node (ref "X2") (pin "1") (pinfunction "1_1") (pintype "passive"))
    )
    (net (code "78") (name "/X32_OUT") (class "Default")
      (node (ref "C21") (pin "1") (pinfunction "1_1") (pintype "passive"))
      (node (ref "U1") (pin "32") (pinfunction "PF.4/X32_OUT_32") (pintype "passive"))
      (node (ref "X2") (pin "2") (pinfunction "2_2") (pintype "passive"))
    )
    (net (code "79") (name "/XT1_IN") (class "Default")
      (node (ref "C18") (pin "1") (pinfunction "1_1") (pintype "passive"))
      (node (ref "U1") (pin "37") (pinfunction "PF.3/XT1_IN_37") (pintype "passive"))
      (node (ref "X1") (pin "1") (pinfunction "S_1") (pintype "passive"))
    )
    (net (code "80") (name "/XT1_OUT") (class "Default")
      (node (ref "C19") (pin "1") (pinfunction "1_1") (pintype "passive"))
      (node (ref "U1") (pin "38") (pinfunction "PF.2/XT1_OUT_38") (pintype "passive"))
      (node (ref "X1") (pin "3") (pinfunction "S_3") (pintype "passive"))
    )
    (net (code "81") (name "/Y_LED") (class "Default")
      (node (ref "R11") (pin "1") (pinfunction "1_1") (pintype "passive"))
      (node (ref "U1") (pin "4") (pinfunction "PB.2/EPWM0_CH3_4") (pintype "passive"))
    )
    (net (code "82") (name "/nRESET") (class "Default")
      (node (ref "C22") (pin "1") (pinfunction "1_1") (pintype "passive"))
      (node (ref "R2") (pin "2") (pinfunction "2_2") (pintype "passive"))
      (node (ref "RSTN") (pin "1") (pinfunction "1_1") (pintype "passive"))
      (node (ref "SW2") (pin "1") (pinfunction "1_1") (pintype "passive"))
      (node (ref "U1") (pin "64") (pinfunction "nRESET_64") (pintype "passive"))
    )
    (net (code "83") (name "3.3V") (class "Default")
      (node (ref "3V3") (pin "1") (pinfunction "1_1") (pintype "passive"))
      (node (ref "C10") (pin "2") (pinfunction "2_2") (pintype "passive"))
      (node (ref "C11") (pin "2") (pinfunction "2_2") (pintype "passive"))
      (node (ref "C16") (pin "1") (pinfunction "1_1") (pintype "passive"))
      (node (ref "C17") (pin "1") (pinfunction "1_1") (pintype "passive"))
      (node (ref "C23") (pin "1") (pinfunction "1_1") (pintype "passive"))
      (node (ref "C24") (pin "1") (pinfunction "1_1") (pintype "passive"))
      (node (ref "C3") (pin "1") (pintype "passive"))
      (node (ref "C31") (pin "1") (pinfunction "1_1") (pintype "passive"))
      (node (ref "C33") (pin "1") (pinfunction "1_1") (pintype "passive"))
      (node (ref "C36") (pin "1") (pinfunction "1_1") (pintype "passive"))
      (node (ref "C38") (pin "1") (pinfunction "1_1") (pintype "passive"))
      (node (ref "C39") (pin "1") (pinfunction "1_1") (pintype "passive"))
      (node (ref "C4") (pin "1") (pintype "passive"))
      (node (ref "C5") (pin "2") (pinfunction "2_2") (pintype "passive"))
      (node (ref "C6") (pin "2") (pinfunction "2_2") (pintype "passive"))
      (node (ref "C7") (pin "2") (pinfunction "2_2") (pintype "passive"))
      (node (ref "C8") (pin "2") (pinfunction "2_2") (pintype "passive"))
      (node (ref "C9") (pin "2") (pinfunction "2_2") (pintype "passive"))
      (node (ref "D3") (pin "2") (pinfunction "K_2") (pintype "passive"))
      (node (ref "I2C") (pin "2") (pinfunction "2_2") (pintype "passive"))
      (node (ref "LS1") (pin "1") (pinfunction "1_1") (pintype "passive"))
      (node (ref "P1") (pin "27") (pinfunction "27_27") (pintype "passive"))
      (node (ref "P1") (pin "28") (pinfunction "28_28") (pintype "passive"))
      (node (ref "P1") (pin "29") (pinfunction "29_29") (pintype "passive"))
      (node (ref "P1") (pin "30") (pinfunction "30_30") (pintype "passive"))
      (node (ref "P1") (pin "31") (pinfunction "31_31") (pintype "passive"))
      (node (ref "P1") (pin "32") (pinfunction "32_32") (pintype "passive"))
      (node (ref "P2") (pin "27") (pinfunction "27_27") (pintype "passive"))
      (node (ref "P2") (pin "28") (pinfunction "28_28") (pintype "passive"))
      (node (ref "P2") (pin "29") (pinfunction "29_29") (pintype "passive"))
      (node (ref "P2") (pin "30") (pinfunction "30_30") (pintype "passive"))
      (node (ref "P2") (pin "31") (pinfunction "31_31") (pintype "passive"))
      (node (ref "P2") (pin "32") (pinfunction "32_32") (pintype "passive"))
      (node (ref "Q1") (pin "1") (pinfunction "1_1") (pintype "passive"))
      (node (ref "R12") (pin "1") (pinfunction "1_1") (pintype "passive"))
      (node (ref "R12") (pin "2") (pinfunction "2_2") (pintype "passive"))
      (node (ref "R13") (pin "2") (pinfunction "2_2") (pintype "passive"))
      (node (ref "R14") (pin "1") (pinfunction "1_1") (pintype "passive"))
      (node (ref "R15") (pin "1") (pinfunction "1_1") (pintype "passive"))
      (node (ref "R16") (pin "1") (pinfunction "1_1") (pintype "passive"))
      (node (ref "R17") (pin "1") (pinfunction "1_1") (pintype "passive"))
      (node (ref "R2") (pin "1") (pinfunction "1_1") (pintype "passive"))
      (node (ref "R20") (pin "1") (pinfunction "1_1") (pintype "passive"))
      (node (ref "R22") (pin "2") (pinfunction "2_2") (pintype "passive"))
      (node (ref "R24") (pin "2") (pinfunction "2_2") (pintype "passive"))
      (node (ref "R26") (pin "2") (pinfunction "2_2") (pintype "passive"))
      (node (ref "R28") (pin "2") (pinfunction "2_2") (pintype "passive"))
      (node (ref "R3") (pin "1") (pinfunction "1_1") (pintype "passive"))
      (node (ref "R4") (pin "1") (pinfunction "1_1") (pintype "passive"))
      (node (ref "R5") (pin "1") (pinfunction "1_1") (pintype "passive"))
      (node (ref "RGB") (pin "2") (pinfunction "2_2") (pintype "passive"))
      (node (ref "U1") (pin "104") (pinfunction "VDD_104") (pintype "passive"))
      (node (ref "U1") (pin "114") (pinfunction "VDD_114") (pintype "passive"))
      (node (ref "U1") (pin "12") (pinfunction "VDD_12") (pintype "passive"))
      (node (ref "U1") (pin "120") (pinfunction "AVDD_120") (pintype "passive"))
      (node (ref "U1") (pin "30") (pinfunction "VDD_30") (pintype "passive"))
      (node (ref "U1") (pin "40") (pinfunction "VDD_40") (pintype "passive"))
      (node (ref "U1") (pin "53") (pinfunction "VDD_53") (pintype "passive"))
      (node (ref "U1") (pin "61") (pinfunction "VDDIO_61") (pintype "passive"))
      (node (ref "U1") (pin "76") (pinfunction "VDD_76") (pintype "passive"))
      (node (ref "U1") (pin "90") (pinfunction "VDD_90") (pintype "passive"))
      (node (ref "U2") (pin "5") (pinfunction "Vout_5") (pintype "passive"))
      (node (ref "U3") (pin "8") (pinfunction "VDD_8") (pintype "passive"))
      (node (ref "U4") (pin "6") (pinfunction "VDD_6") (pintype "passive"))
      (node (ref "U5") (pin "3") (pinfunction "VBAT_3") (pintype "passive"))
      (node (ref "UART0") (pin "2") (pinfunction "2_2") (pintype "passive"))
    )
    (net (code "84") (name "GND") (class "Default")
      (node (ref "A") (pin "2") (pinfunction "2_2") (pintype "passive"))
      (node (ref "B") (pin "2") (pinfunction "2_2") (pintype "passive"))
      (node (ref "C") (pin "2") (pinfunction "2_2") (pintype "passive"))
      (node (ref "C1") (pin "2") (pintype "passive"))
      (node (ref "C10") (pin "1") (pinfunction "1_1") (pintype "passive"))
      (node (ref "C11") (pin "1") (pinfunction "1_1") (pintype "passive"))
      (node (ref "C12") (pin "1") (pinfunction "1_1") (pintype "passive"))
      (node (ref "C13") (pin "1") (pinfunction "1_1") (pintype "passive"))
      (node (ref "C14") (pin "1") (pinfunction "1_1") (pintype "passive"))
      (node (ref "C15") (pin "1") (pinfunction "1_1") (pintype "passive"))
      (node (ref "C16") (pin "2") (pinfunction "2_2") (pintype "passive"))
      (node (ref "C17") (pin "2") (pinfunction "2_2") (pintype "passive"))
      (node (ref "C18") (pin "2") (pinfunction "2_2") (pintype "passive"))
      (node (ref "C19") (pin "2") (pinfunction "2_2") (pintype "passive"))
      (node (ref "C2") (pin "2") (pintype "passive"))
      (node (ref "C20") (pin "2") (pinfunction "2_2") (pintype "passive"))
      (node (ref "C21") (pin "2") (pinfunction "2_2") (pintype "passive"))
      (node (ref "C22") (pin "2") (pinfunction "2_2") (pintype "passive"))
      (node (ref "C23") (pin "2") (pinfunction "2_2") (pintype "passive"))
      (node (ref "C24") (pin "2") (pinfunction "2_2") (pintype "passive"))
      (node (ref "C25") (pin "2") (pinfunction "2_2") (pintype "passive"))
      (node (ref "C26") (pin "2") (pinfunction "2_2") (pintype "passive"))
      (node (ref "C27") (pin "2") (pinfunction "2_2") (pintype "passive"))
      (node (ref "C28") (pin "2") (pinfunction "2_2") (pintype "passive"))
      (node (ref "C29") (pin "2") (pinfunction "2_2") (pintype "passive"))
      (node (ref "C3") (pin "2") (pintype "passive"))
      (node (ref "C30") (pin "2") (pinfunction "2_2") (pintype "passive"))
      (node (ref "C31") (pin "2") (pinfunction "2_2") (pintype "passive"))
      (node (ref "C33") (pin "2") (pinfunction "2_2") (pintype "passive"))
      (node (ref "C36") (pin "2") (pinfunction "2_2") (pintype "passive"))
      (node (ref "C38") (pin "2") (pinfunction "2_2") (pintype "passive"))
      (node (ref "C39") (pin "2") (pinfunction "2_2") (pintype "passive"))
      (node (ref "C4") (pin "2") (pintype "passive"))
      (node (ref "C40") (pin "2") (pinfunction "2_2") (pintype "passive"))
      (node (ref "C5") (pin "1") (pinfunction "1_1") (pintype "passive"))
      (node (ref "C6") (pin "1") (pinfunction "1_1") (pintype "passive"))
      (node (ref "C7") (pin "1") (pinfunction "1_1") (pintype "passive"))
      (node (ref "C8") (pin "1") (pinfunction "1_1") (pintype "passive"))
      (node (ref "C9") (pin "1") (pinfunction "1_1") (pintype "passive"))
      (node (ref "D") (pin "2") (pinfunction "2_2") (pintype "passive"))
      (node (ref "D10") (pin "2") (pinfunction "2_2") (pintype "passive"))
      (node (ref "D4") (pin "1") (pinfunction "A_1") (pintype "passive"))
      (node (ref "D5") (pin "1") (pinfunction "A_1") (pintype "passive"))
      (node (ref "D6") (pin "2") (pinfunction "K_2") (pintype "passive"))
      (node (ref "GND") (pin "1") (pinfunction "1_1") (pintype "passive"))
      (node (ref "I2C") (pin "1") (pinfunction "1_1") (pintype "passive"))
      (node (ref "J1") (pin "2") (pinfunction "2_2") (pintype "passive"))
      (node (ref "J1") (pin "P1") (pinfunction "P1_P1") (pintype "passive"))
      (node (ref "J1") (pin "P2") (pinfunction "P2_P2") (pintype "passive"))
      (node (ref "J3") (pin "5") (pinfunction "GND_5") (pintype "power_in"))
      (node (ref "J3") (pin "H0") (pinfunction "H0_H0") (pintype "power_in"))
      (node (ref "J3") (pin "H1") (pinfunction "H1_H1") (pintype "power_in"))
      (node (ref "J3") (pin "H2") (pinfunction "H2_H2") (pintype "power_in"))
      (node (ref "J3") (pin "H3") (pinfunction "H3_H3") (pintype "power_in"))
      (node (ref "LED1") (pin "2") (pinfunction "K_2") (pintype "passive"))
      (node (ref "LED2") (pin "2") (pinfunction "K_2") (pintype "passive"))
      (node (ref "LED3") (pin "2") (pinfunction "K_2") (pintype "passive"))
      (node (ref "LED4") (pin "2") (pinfunction "K_2") (pintype "passive"))
      (node (ref "MICL") (pin "2") (pinfunction "2_2") (pintype "passive"))
      (node (ref "MICR") (pin "2") (pinfunction "2_2") (pintype "passive"))
      (node (ref "P1") (pin "35") (pinfunction "35_35") (pintype "passive"))
      (node (ref "P1") (pin "36") (pinfunction "36_36") (pintype "passive"))
      (node (ref "P1") (pin "37") (pinfunction "37_37") (pintype "passive"))
      (node (ref "P1") (pin "38") (pinfunction "38_38") (pintype "passive"))
      (node (ref "P1") (pin "39") (pinfunction "39_39") (pintype "passive"))
      (node (ref "P1") (pin "40") (pinfunction "40_40") (pintype "passive"))
      (node (ref "P2") (pin "35") (pinfunction "35_35") (pintype "passive"))
      (node (ref "P2") (pin "36") (pinfunction "36_36") (pintype "passive"))
      (node (ref "P2") (pin "37") (pinfunction "37_37") (pintype "passive"))
      (node (ref "P2") (pin "38") (pinfunction "38_38") (pintype "passive"))
      (node (ref "P2") (pin "39") (pinfunction "39_39") (pintype "passive"))
      (node (ref "P2") (pin "40") (pinfunction "40_40") (pintype "passive"))
      (node (ref "Q2") (pin "2") (pinfunction "E_2") (pintype "passive"))
      (node (ref "Q3") (pin "E") (pintype "passive"))
      (node (ref "Q4") (pin "E") (pintype "passive"))
      (node (ref "R21") (pin "1") (pinfunction "1_1") (pintype "passive"))
      (node (ref "R25") (pin "1") (pinfunction "1_1") (pintype "passive"))
      (node (ref "R31") (pin "1") (pintype "passive"))
      (node (ref "R6") (pin "2") (pinfunction "2_2") (pintype "passive"))
      (node (ref "RGB") (pin "1") (pinfunction "1_1") (pintype "passive"))
      (node (ref "SW2") (pin "2") (pinfunction "2_2") (pintype "passive"))
      (node (ref "U1") (pin "103") (pinfunction "VSS_103") (pintype "passive"))
      (node (ref "U1") (pin "11") (pinfunction "VSS_11") (pintype "passive"))
      (node (ref "U1") (pin "112") (pinfunction "VSS_112") (pintype "passive"))
      (node (ref "U1") (pin "122") (pinfunction "AVSS_122") (pintype "passive"))
      (node (ref "U1") (pin "39") (pinfunction "VSS_39") (pintype "passive"))
      (node (ref "U1") (pin "52") (pinfunction "VSS_52") (pintype "passive"))
      (node (ref "U1") (pin "75") (pinfunction "VSS_75") (pintype "passive"))
      (node (ref "U1") (pin "93") (pinfunction "VSS_93") (pintype "passive"))
      (node (ref "U2") (pin "2") (pinfunction "Vss_2") (pintype "passive"))
      (node (ref "U3") (pin "4") (pinfunction "GND_4") (pintype "passive"))
      (node (ref "U4") (pin "3") (pinfunction "GND_3") (pintype "passive"))
      (node (ref "U5") (pin "1") (pinfunction "GND_1") (pintype "passive"))
      (node (ref "U5") (pin "15") (pinfunction "GND_15") (pintype "passive"))
      (node (ref "UART0") (pin "1") (pinfunction "1_1") (pintype "passive"))
      (node (ref "V-") (pin "1") (pinfunction "1_1") (pintype "passive"))
      (node (ref "X1") (pin "2") (pinfunction "GND_2") (pintype "passive"))
      (node (ref "X1") (pin "4") (pinfunction "GND_4") (pintype "passive"))
    )
    (net (code "85") (name "Net-(C32-Pad2)") (class "Default")
      (node (ref "C32") (pin "2") (pinfunction "2_2") (pintype "passive"))
      (node (ref "Q3") (pin "C") (pintype "passive"))
      (node (ref "R22") (pin "1") (pinfunction "1_1") (pintype "passive"))
      (node (ref "R23") (pin "2") (pinfunction "2_2") (pintype "passive"))
    )
    (net (code "86") (name "Net-(C34-Pad1)") (class "Default")
      (node (ref "C34") (pin "1") (pinfunction "1_1") (pintype "passive"))
      (node (ref "Q3") (pin "B") (pintype "passive"))
      (node (ref "R23") (pin "1") (pinfunction "1_1") (pintype "passive"))
    )
    (net (code "87") (name "Net-(C34-Pad2)") (class "Default")
      (node (ref "C34") (pin "2") (pinfunction "2_2") (pintype "passive"))
      (node (ref "MICL") (pin "1") (pinfunction "1_1") (pintype "passive"))
      (node (ref "R24") (pin "1") (pinfunction "1_1") (pintype "passive"))
    )
    (net (code "88") (name "Net-(C35-Pad2)") (class "Default")
      (node (ref "C35") (pin "2") (pinfunction "2_2") (pintype "passive"))
      (node (ref "Q4") (pin "C") (pintype "passive"))
      (node (ref "R26") (pin "1") (pinfunction "1_1") (pintype "passive"))
      (node (ref "R27") (pin "2") (pinfunction "2_2") (pintype "passive"))
    )
    (net (code "89") (name "Net-(C37-Pad1)") (class "Default")
      (node (ref "C37") (pin "1") (pinfunction "1_1") (pintype "passive"))
      (node (ref "Q4") (pin "B") (pintype "passive"))
      (node (ref "R27") (pin "1") (pinfunction "1_1") (pintype "passive"))
    )
    (net (code "90") (name "Net-(C37-Pad2)") (class "Default")
      (node (ref "C37") (pin "2") (pinfunction "2_2") (pintype "passive"))
      (node (ref "MICR") (pin "1") (pinfunction "1_1") (pintype "passive"))
      (node (ref "R28") (pin "1") (pinfunction "1_1") (pintype "passive"))
    )
    (net (code "91") (name "Net-(D3-A)") (class "Default")
      (node (ref "D3") (pin "1") (pinfunction "A_1") (pintype "passive"))
      (node (ref "LS1") (pin "2") (pinfunction "2_2") (pintype "passive"))
      (node (ref "Q2") (pin "3") (pinfunction "C_3") (pintype "passive"))
    )
    (net (code "92") (name "Net-(D6-A)") (class "Default")
      (node (ref "D6") (pin "1") (pinfunction "A_1") (pintype "passive"))
      (node (ref "R29") (pin "2") (pintype "passive"))
    )
    (net (code "93") (name "Net-(J3-UDC+)") (class "Default")
      (node (ref "D10") (pin "1") (pinfunction "1_1") (pintype "passive"))
      (node (ref "D10") (pin "6") (pinfunction "6_6") (pintype "passive"))
      (node (ref "J3") (pin "3") (pinfunction "UDC+_3") (pintype "bidirectional"))
      (node (ref "R18") (pin "1") (pinfunction "1_1") (pintype "passive"))
    )
    (net (code "94") (name "Net-(J3-UDC-)") (class "Default")
      (node (ref "D10") (pin "3") (pinfunction "3_3") (pintype "passive"))
      (node (ref "D10") (pin "4") (pinfunction "4_4") (pintype "passive"))
      (node (ref "J3") (pin "2") (pinfunction "UDC-_2") (pintype "bidirectional"))
      (node (ref "R19") (pin "1") (pinfunction "1_1") (pintype "passive"))
    )
    (net (code "95") (name "Net-(J3-VBUS)") (class "Default")
      (node (ref "C29") (pin "1") (pinfunction "1_1") (pintype "passive"))
      (node (ref "C30") (pin "1") (pinfunction "1_1") (pintype "passive"))
      (node (ref "J3") (pin "1") (pinfunction "VBUS_1") (pintype "bidirectional"))
      (node (ref "L1") (pin "1") (pinfunction "1_1") (pintype "passive"))
    )
    (net (code "96") (name "Net-(LED1-A)") (class "Default")
      (node (ref "LED1") (pin "1") (pinfunction "A_1") (pintype "passive"))
      (node (ref "R8") (pin "2") (pinfunction "2_2") (pintype "passive"))
    )
    (net (code "97") (name "Net-(LED2-A)") (class "Default")
      (node (ref "LED2") (pin "1") (pinfunction "A_1") (pintype "passive"))
      (node (ref "R9") (pin "2") (pinfunction "2_2") (pintype "passive"))
    )
    (net (code "98") (name "Net-(LED3-A)") (class "Default")
      (node (ref "LED3") (pin "1") (pinfunction "A_1") (pintype "passive"))
      (node (ref "R10") (pin "2") (pinfunction "2_2") (pintype "passive"))
    )
    (net (code "99") (name "Net-(LED4-A)") (class "Default")
      (node (ref "LED4") (pin "1") (pinfunction "A_1") (pintype "passive"))
      (node (ref "R11") (pin "2") (pinfunction "2_2") (pintype "passive"))
    )
    (net (code "100") (name "Net-(Q2-B)") (class "Default")
      (node (ref "Q2") (pin "1") (pinfunction "B_1") (pintype "passive"))
      (node (ref "R7") (pin "2") (pinfunction "2_2") (pintype "passive"))
    )
    (net (code "101") (name "USB_VBUS") (class "Default")
      (node (ref "D10") (pin "5") (pinfunction "5_5") (pintype "passive"))
      (node (ref "L1") (pin "2") (pinfunction "2_2") (pintype "passive"))
      (node (ref "U1") (pin "85") (pinfunction "PA.12/USB_VBUS_85") (pintype "passive"))
    )
    (net (code "102") (name "USB_VCC") (class "Default")
      (node (ref "D2") (pin "1") (pinfunction "A_1") (pintype "passive"))
    )
    (net (code "103") (name "VIN") (class "Default")
      (node (ref "C1") (pin "1") (pintype "passive"))
      (node (ref "C2") (pin "1") (pintype "passive"))
      (node (ref "D1") (pin "2") (pinfunction "K_2") (pintype "passive"))
      (node (ref "D2") (pin "2") (pinfunction "K_2") (pintype "passive"))
      (node (ref "R30") (pin "2") (pintype "passive"))
      (node (ref "U2") (pin "1") (pinfunction "Vin_1") (pintype "passive"))
      (node (ref "U2") (pin "3") (pinfunction "CE_3") (pintype "passive"))
    )
    (net (code "104") (name "unconnected-(J3-ID-Pad4)") (class "Default")
      (node (ref "J3") (pin "4") (pinfunction "ID_4") (pintype "bidirectional"))
    )
    (net (code "105") (name "unconnected-(U1-NC-Pad89)") (class "Default")
      (node (ref "U1") (pin "89") (pinfunction "NC_89") (pintype "passive+no_connect"))
    )
    (net (code "106") (name "unconnected-(U1-NC-Pad91)") (class "Default")
      (node (ref "U1") (pin "91") (pinfunction "NC_91") (pintype "passive+no_connect"))
    )
    (net (code "107") (name "unconnected-(U1-NC-Pad92)") (class "Default")
      (node (ref "U1") (pin "92") (pinfunction "NC_92") (pintype "passive+no_connect"))
    )
    (net (code "108") (name "unconnected-(U1-NC-Pad94)") (class "Default")
      (node (ref "U1") (pin "94") (pinfunction "NC_94") (pintype "passive+no_connect"))
    )
    (net (code "109") (name "unconnected-(U1-NC-Pad96)") (class "Default")
      (node (ref "U1") (pin "96") (pinfunction "NC_96") (pintype "passive+no_connect"))
    )
    (net (code "110") (name "unconnected-(U1-PA.4{slash}QSPI0_MOSI1-Pad56)") (class "Default")
      (node (ref "U1") (pin "56") (pinfunction "PA.4/QSPI0_MOSI1_56") (pintype "passive+no_connect"))
    )
    (net (code "111") (name "unconnected-(U1-PA.5{slash}QSPI0_MISO1-Pad55)") (class "Default")
      (node (ref "U1") (pin "55") (pinfunction "PA.5/QSPI0_MISO1_55") (pintype "passive+no_connect"))
    )
    (net (code "112") (name "unconnected-(U1-PA.10{slash}BPWM0_CH1-Pad14)") (class "Default")
      (node (ref "U1") (pin "14") (pinfunction "PA.10/BPWM0_CH1_14") (pintype "passive+no_connect"))
    )
    (net (code "113") (name "unconnected-(U1-PA.11{slash}BPWM0_CH0-Pad13)") (class "Default")
      (node (ref "U1") (pin "13") (pinfunction "PA.11/BPWM0_CH0_13") (pintype "passive+no_connect"))
    )
    (net (code "114") (name "unconnected-(U1-PC.8{slash}BPWM1_CH4-Pad47)") (class "Default")
      (node (ref "U1") (pin "47") (pinfunction "PC.8/BPWM1_CH4_47") (pintype "passive+no_connect"))
    )
    (net (code "115") (name "unconnected-(U1-PC.9{slash}UART3_RXD-Pad8)") (class "Default")
      (node (ref "U1") (pin "8") (pinfunction "PC.9/UART3_RXD_8") (pintype "passive+no_connect"))
    )
    (net (code "116") (name "unconnected-(U1-PC.10{slash}ECAP1_IC0-Pad7)") (class "Default")
      (node (ref "U1") (pin "7") (pinfunction "PC.10/ECAP1_IC0_7") (pintype "passive+no_connect"))
    )
    (net (code "117") (name "unconnected-(U1-PC.11{slash}ECAP1_IC1-Pad6)") (class "Default")
      (node (ref "U1") (pin "6") (pinfunction "PC.11/ECAP1_IC1_6") (pintype "passive+no_connect"))
    )
    (net (code "118") (name "unconnected-(U1-PC.12{slash}ECAP1_IC2-Pad5)") (class "Default")
      (node (ref "U1") (pin "5") (pinfunction "PC.12/ECAP1_IC2_5") (pintype "passive+no_connect"))
    )
    (net (code "119") (name "unconnected-(U1-PC.13{slash}BPWM0_CH4-Pad17)") (class "Default")
      (node (ref "U1") (pin "17") (pinfunction "PC.13/BPWM0_CH4_17") (pintype "passive+no_connect"))
    )
    (net (code "120") (name "unconnected-(U1-PD.10{slash}OPA2_P{slash}EBI_nCS2{slash}UART1_RXD{slash}QEI0_B{slash}INT7-Pad20)") (class "Default")
      (node (ref "U1") (pin "20") (pinfunction "PD.10/OPA2_P/EBI_nCS2/UART1_RXD/QEI0_B/INT7_20") (pintype "passive+no_connect"))
    )
    (net (code "121") (name "unconnected-(U1-PD.11{slash}OPA2_N{slash}EBI_nCS1{slash}UART1_TXD{slash}QEI0_A{slash}INT6-Pad19)") (class "Default")
      (node (ref "U1") (pin "19") (pinfunction "PD.11/OPA2_N/EBI_nCS1/UART1_TXD/QEI0_A/INT6_19") (pintype "passive+no_connect"))
    )
    (net (code "122") (name "unconnected-(U1-PD.12{slash}BPWM0_CH5-Pad18)") (class "Default")
      (node (ref "U1") (pin "18") (pinfunction "PD.12/BPWM0_CH5_18") (pintype "passive+no_connect"))
    )
    (net (code "123") (name "unconnected-(U1-PE.8{slash}I2S0_BCLK-Pad41)") (class "Default")
      (node (ref "U1") (pin "41") (pinfunction "PE.8/I2S0_BCLK_41") (pintype "passive+no_connect"))
    )
    (net (code "124") (name "unconnected-(U1-PE.9{slash}I2S0_MCLK-Pad42)") (class "Default")
      (node (ref "U1") (pin "42") (pinfunction "PE.9/I2S0_MCLK_42") (pintype "passive+no_connect"))
    )
    (net (code "125") (name "unconnected-(U1-PE.10{slash}I2S0_DI-Pad43)") (class "Default")
      (node (ref "U1") (pin "43") (pinfunction "PE.10/I2S0_DI_43") (pintype "passive+no_connect"))
    )
    (net (code "126") (name "unconnected-(U1-PE.11{slash}I2S0_DO-Pad44)") (class "Default")
      (node (ref "U1") (pin "44") (pinfunction "PE.11/I2S0_DO_44") (pintype "passive+no_connect"))
    )
    (net (code "127") (name "unconnected-(U1-PE.12{slash}SPI2_I2SMCLK-Pad45)") (class "Default")
      (node (ref "U1") (pin "45") (pinfunction "PE.12/SPI2_I2SMCLK_45") (pintype "passive+no_connect"))
    )
    (net (code "128") (name "unconnected-(U1-PF.7{slash}SPI0_MISO-Pad28)") (class "Default")
      (node (ref "U1") (pin "28") (pinfunction "PF.7/SPI0_MISO_28") (pintype "passive+no_connect"))
    )
    (net (code "129") (name "unconnected-(U1-PF.8{slash}SPI0_CLK-Pad27)") (class "Default")
      (node (ref "U1") (pin "27") (pinfunction "PF.8/SPI0_CLK_27") (pintype "passive+no_connect"))
    )
    (net (code "130") (name "unconnected-(U1-PF.9{slash}SPI0_SS-Pad26)") (class "Default")
      (node (ref "U1") (pin "26") (pinfunction "PF.9/SPI0_SS_26") (pintype "passive+no_connect"))
    )
    (net (code "131") (name "unconnected-(U1-PF.10{slash}SPI0_I2SMCLK-Pad25)") (class "Default")
      (node (ref "U1") (pin "25") (pinfunction "PF.10/SPI0_I2SMCLK_25") (pintype "passive+no_connect"))
    )
    (net (code "132") (name "unconnected-(U1-PG.2{slash}SPI2_SS-Pad21)") (class "Default")
      (node (ref "U1") (pin "21") (pinfunction "PG.2/SPI2_SS_21") (pintype "passive+no_connect"))
    )
    (net (code "133") (name "unconnected-(U1-PG.3{slash}SPI2_CLK-Pad22)") (class "Default")
      (node (ref "U1") (pin "22") (pinfunction "PG.3/SPI2_CLK_22") (pintype "passive+no_connect"))
    )
    (net (code "134") (name "unconnected-(U1-PG.4{slash}SPI2_MISO-Pad23)") (class "Default")
      (node (ref "U1") (pin "23") (pinfunction "PG.4/SPI2_MISO_23") (pintype "passive+no_connect"))
    )
    (net (code "135") (name "unconnected-(U1-PH.4{slash}SPI1_MISO-Pad33)") (class "Default")
      (node (ref "U1") (pin "33") (pinfunction "PH.4/SPI1_MISO_33") (pintype "passive+no_connect"))
    )
    (net (code "136") (name "unconnected-(U1-PH.5{slash}SPI1_MOSI-Pad34)") (class "Default")
      (node (ref "U1") (pin "34") (pinfunction "PH.5/SPI1_MOSI_34") (pintype "passive+no_connect"))
    )
    (net (code "137") (name "unconnected-(U1-PH.6{slash}SPI1_CLK-Pad35)") (class "Default")
      (node (ref "U1") (pin "35") (pinfunction "PH.6/SPI1_CLK_35") (pintype "passive+no_connect"))
    )
    (net (code "138") (name "unconnected-(U1-PH.7{slash}SPI1_SS-Pad36)") (class "Default")
      (node (ref "U1") (pin "36") (pinfunction "PH.7/SPI1_SS_36") (pintype "passive+no_connect"))
    )
    (net (code "139") (name "unconnected-(U1-PH.8{slash}I2C1_SMBAL-Pad107)") (class "Default")
      (node (ref "U1") (pin "107") (pinfunction "PH.8/I2C1_SMBAL_107") (pintype "passive+no_connect"))
    )
    (net (code "140") (name "unconnected-(U1-PH.9{slash}I2C1_SMBSUS-Pad108)") (class "Default")
      (node (ref "U1") (pin "108") (pinfunction "PH.9/I2C1_SMBSUS_108") (pintype "passive+no_connect"))
    )
    (net (code "141") (name "unconnected-(U2-NC-Pad4)") (class "Default")
      (node (ref "U2") (pin "4") (pinfunction "NC_4") (pintype "passive+no_connect"))
    )
    (net (code "142") (name "unconnected-(U4-NC-Pad2)") (class "Default")
      (node (ref "U4") (pin "2") (pinfunction "NC_2") (pintype "passive"))
    )
    (net (code "143") (name "unconnected-(U5-P0_3-Pad4)") (class "Default")
      (node (ref "U5") (pin "4") (pinfunction "P0_3_4") (pintype "passive+no_connect"))
    )
    (net (code "144") (name "unconnected-(U5-P1_0-Pad7)") (class "Default")
      (node (ref "U5") (pin "7") (pinfunction "P1_0_7") (pintype "passive+no_connect"))
    )
    (net (code "145") (name "unconnected-(U5-P1_1-Pad8)") (class "Default")
      (node (ref "U5") (pin "8") (pinfunction "P1_1_8") (pintype "passive+no_connect"))
    )
    (net (code "146") (name "unconnected-(U5-P2_3-Pad10)") (class "Default")
      (node (ref "U5") (pin "10") (pinfunction "P2_3_10") (pintype "passive+no_connect"))
    )
  )
)
